# tiaracon.net
KiCad netlist of a schematic drawn in EAGLE
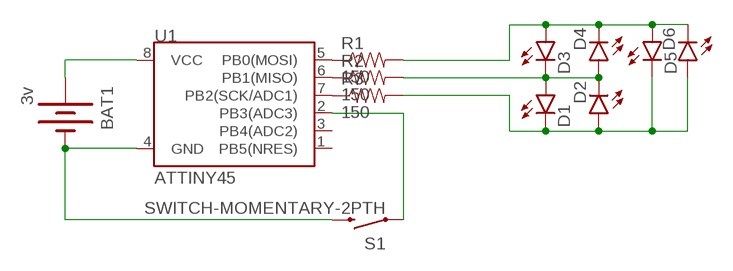
[diagram p0: schematic, sheet 1]

(export (version "E")
  (design (tool "Eeschema 10.0.6"))
  (components
    (comp (ref "BAT1")
      (value "3v")
      (footprint "eagle-import:BATTCOM_20MM_PTH")
      (libsource (lib "eagle-import") (part "BATTERY20PTH"))
    )
    (comp (ref "D1")
      (value "LED3MM")
      (footprint "eagle-import:LED3MM")
      (libsource (lib "eagle-import") (part "LED3MM"))
    )
    (comp (ref "D2")
      (value "LED3MM")
      (footprint "eagle-import:LED3MM")
      (libsource (lib "eagle-import") (part "LED3MM"))
    )
    (comp (ref "D3")
      (value "LED3MM")
      (footprint "eagle-import:LED3MM")
      (libsource (lib "eagle-import") (part "LED3MM"))
    )
    (comp (ref "D4")
      (value "LED3MM")
      (footprint "eagle-import:LED3MM")
      (libsource (lib "eagle-import") (part "LED3MM"))
    )
    (comp (ref "D5")
      (value "LED3MM")
      (footprint "eagle-import:LED3MM")
      (libsource (lib "eagle-import") (part "LED3MM"))
    )
    (comp (ref "D6")
      (value "LED3MM")
      (footprint "eagle-import:LED3MM")
      (libsource (lib "eagle-import") (part "LED3MM"))
    )
    (comp (ref "R1")
      (value "150")
      (footprint "eagle-import:AXIAL-0.4")
      (libsource (lib "eagle-import") (part "RESISTORPTH-1/4W"))
    )
    (comp (ref "R2")
      (value "150")
      (footprint "eagle-import:AXIAL-0.4")
      (libsource (lib "eagle-import") (part "RESISTORPTH-1/4W"))
    )
    (comp (ref "R3")
      (value "150")
      (footprint "eagle-import:AXIAL-0.4")
      (libsource (lib "eagle-import") (part "RESISTORPTH-1/4W"))
    )
    (comp (ref "S1")
      (value "SWITCH-MOMENTARY-2PTH")
      (footprint "eagle-import:TACTILE-PTH")
      (libsource (lib "eagle-import") (part "SWITCH-MOMENTARY-2PTH"))
    )
    (comp (ref "U1")
      (value "ATTINY45")
      (footprint "eagle-import:DIP08")
      (libsource (lib "eagle-import") (part "ATTINY45TINY85-20-DIP"))
    )
  )
  (nets
    (net (code "1") (name "Net-(BAT1-+)") (class "Default")
      (node (ref "BAT1") (pin "1") (pinfunction "+_1") (pintype "power_in"))
      (node (ref "U1") (pin "8") (pinfunction "VCC_8") (pintype "bidirectional"))
    )
    (net (code "2") (name "Net-(BAT1--)") (class "Default")
      (node (ref "BAT1") (pin "2") (pinfunction "-_2") (pintype "power_in"))
      (node (ref "S1") (pin "3") (pinfunction "2_3") (pintype "passive"))
      (node (ref "U1") (pin "4") (pinfunction "GND_4") (pintype "bidirectional"))
    )
    (net (code "3") (name "Net-(D1-C)") (class "Default")
      (node (ref "D1") (pin "K") (pinfunction "C_K") (pintype "passive"))
      (node (ref "D2") (pin "A") (pinfunction "A_A") (pintype "passive"))
      (node (ref "D5") (pin "K") (pinfunction "C_K") (pintype "passive"))
      (node (ref "D6") (pin "A") (pinfunction "A_A") (pintype "passive"))
      (node (ref "R3") (pin "P$2") (pinfunction "2_P$2") (pintype "passive"))
    )
    (net (code "4") (name "Net-(D2-C)") (class "Default")
      (node (ref "D1") (pin "A") (pinfunction "A_A") (pintype "passive"))
      (node (ref "D2") (pin "K") (pinfunction "C_K") (pintype "passive"))
      (node (ref "D3") (pin "K") (pinfunction "C_K") (pintype "passive"))
      (node (ref "D4") (pin "A") (pinfunction "A_A") (pintype "passive"))
      (node (ref "R2") (pin "P$2") (pinfunction "2_P$2") (pintype "passive"))
    )
    (net (code "5") (name "Net-(D4-C)") (class "Default")
      (node (ref "D3") (pin "A") (pinfunction "A_A") (pintype "passive"))
      (node (ref "D4") (pin "K") (pinfunction "C_K") (pintype "passive"))
      (node (ref "D5") (pin "A") (pinfunction "A_A") (pintype "passive"))
      (node (ref "D6") (pin "K") (pinfunction "C_K") (pintype "passive"))
      (node (ref "R1") (pin "P$2") (pinfunction "2_P$2") (pintype "passive"))
    )
    (net (code "6") (name "Net-(R1-1)") (class "Default")
      (node (ref "R1") (pin "P$1") (pinfunction "1_P$1") (pintype "passive"))
      (node (ref "U1") (pin "5") (pinfunction "PB0(MOSI)_5") (pintype "bidirectional"))
    )
    (net (code "7") (name "Net-(R2-1)") (class "Default")
      (node (ref "R2") (pin "P$1") (pinfunction "1_P$1") (pintype "passive"))
      (node (ref "U1") (pin "6") (pinfunction "PB1(MISO)_6") (pintype "bidirectional"))
    )
    (net (code "8") (name "Net-(R3-1)") (class "Default")
      (node (ref "R3") (pin "P$1") (pinfunction "1_P$1") (pintype "passive"))
      (node (ref "U1") (pin "7") (pinfunction "PB2(SCK/ADC1)_7") (pintype "bidirectional"))
    )
    (net (code "9") (name "Net-(U1-PB3(ADC3))") (class "Default")
      (node (ref "S1") (pin "1") (pinfunction "1_1") (pintype "passive"))
      (node (ref "U1") (pin "2") (pinfunction "PB3(ADC3)_2") (pintype "bidirectional"))
    )
    (net (code "10") (name "unconnected-(U1-PB4(ADC2)-Pad3)") (class "Default")
      (node (ref "U1") (pin "3") (pinfunction "PB4(ADC2)_3") (pintype "bidirectional"))
    )
    (net (code "11") (name "unconnected-(U1-PB5(NRES)-Pad1)") (class "Default")
      (node (ref "U1") (pin "1") (pinfunction "PB5(NRES)_1") (pintype "bidirectional"))
    )
  )
)
